# napajeniMOB.net
KiCad netlist of a schematic drawn in EAGLE
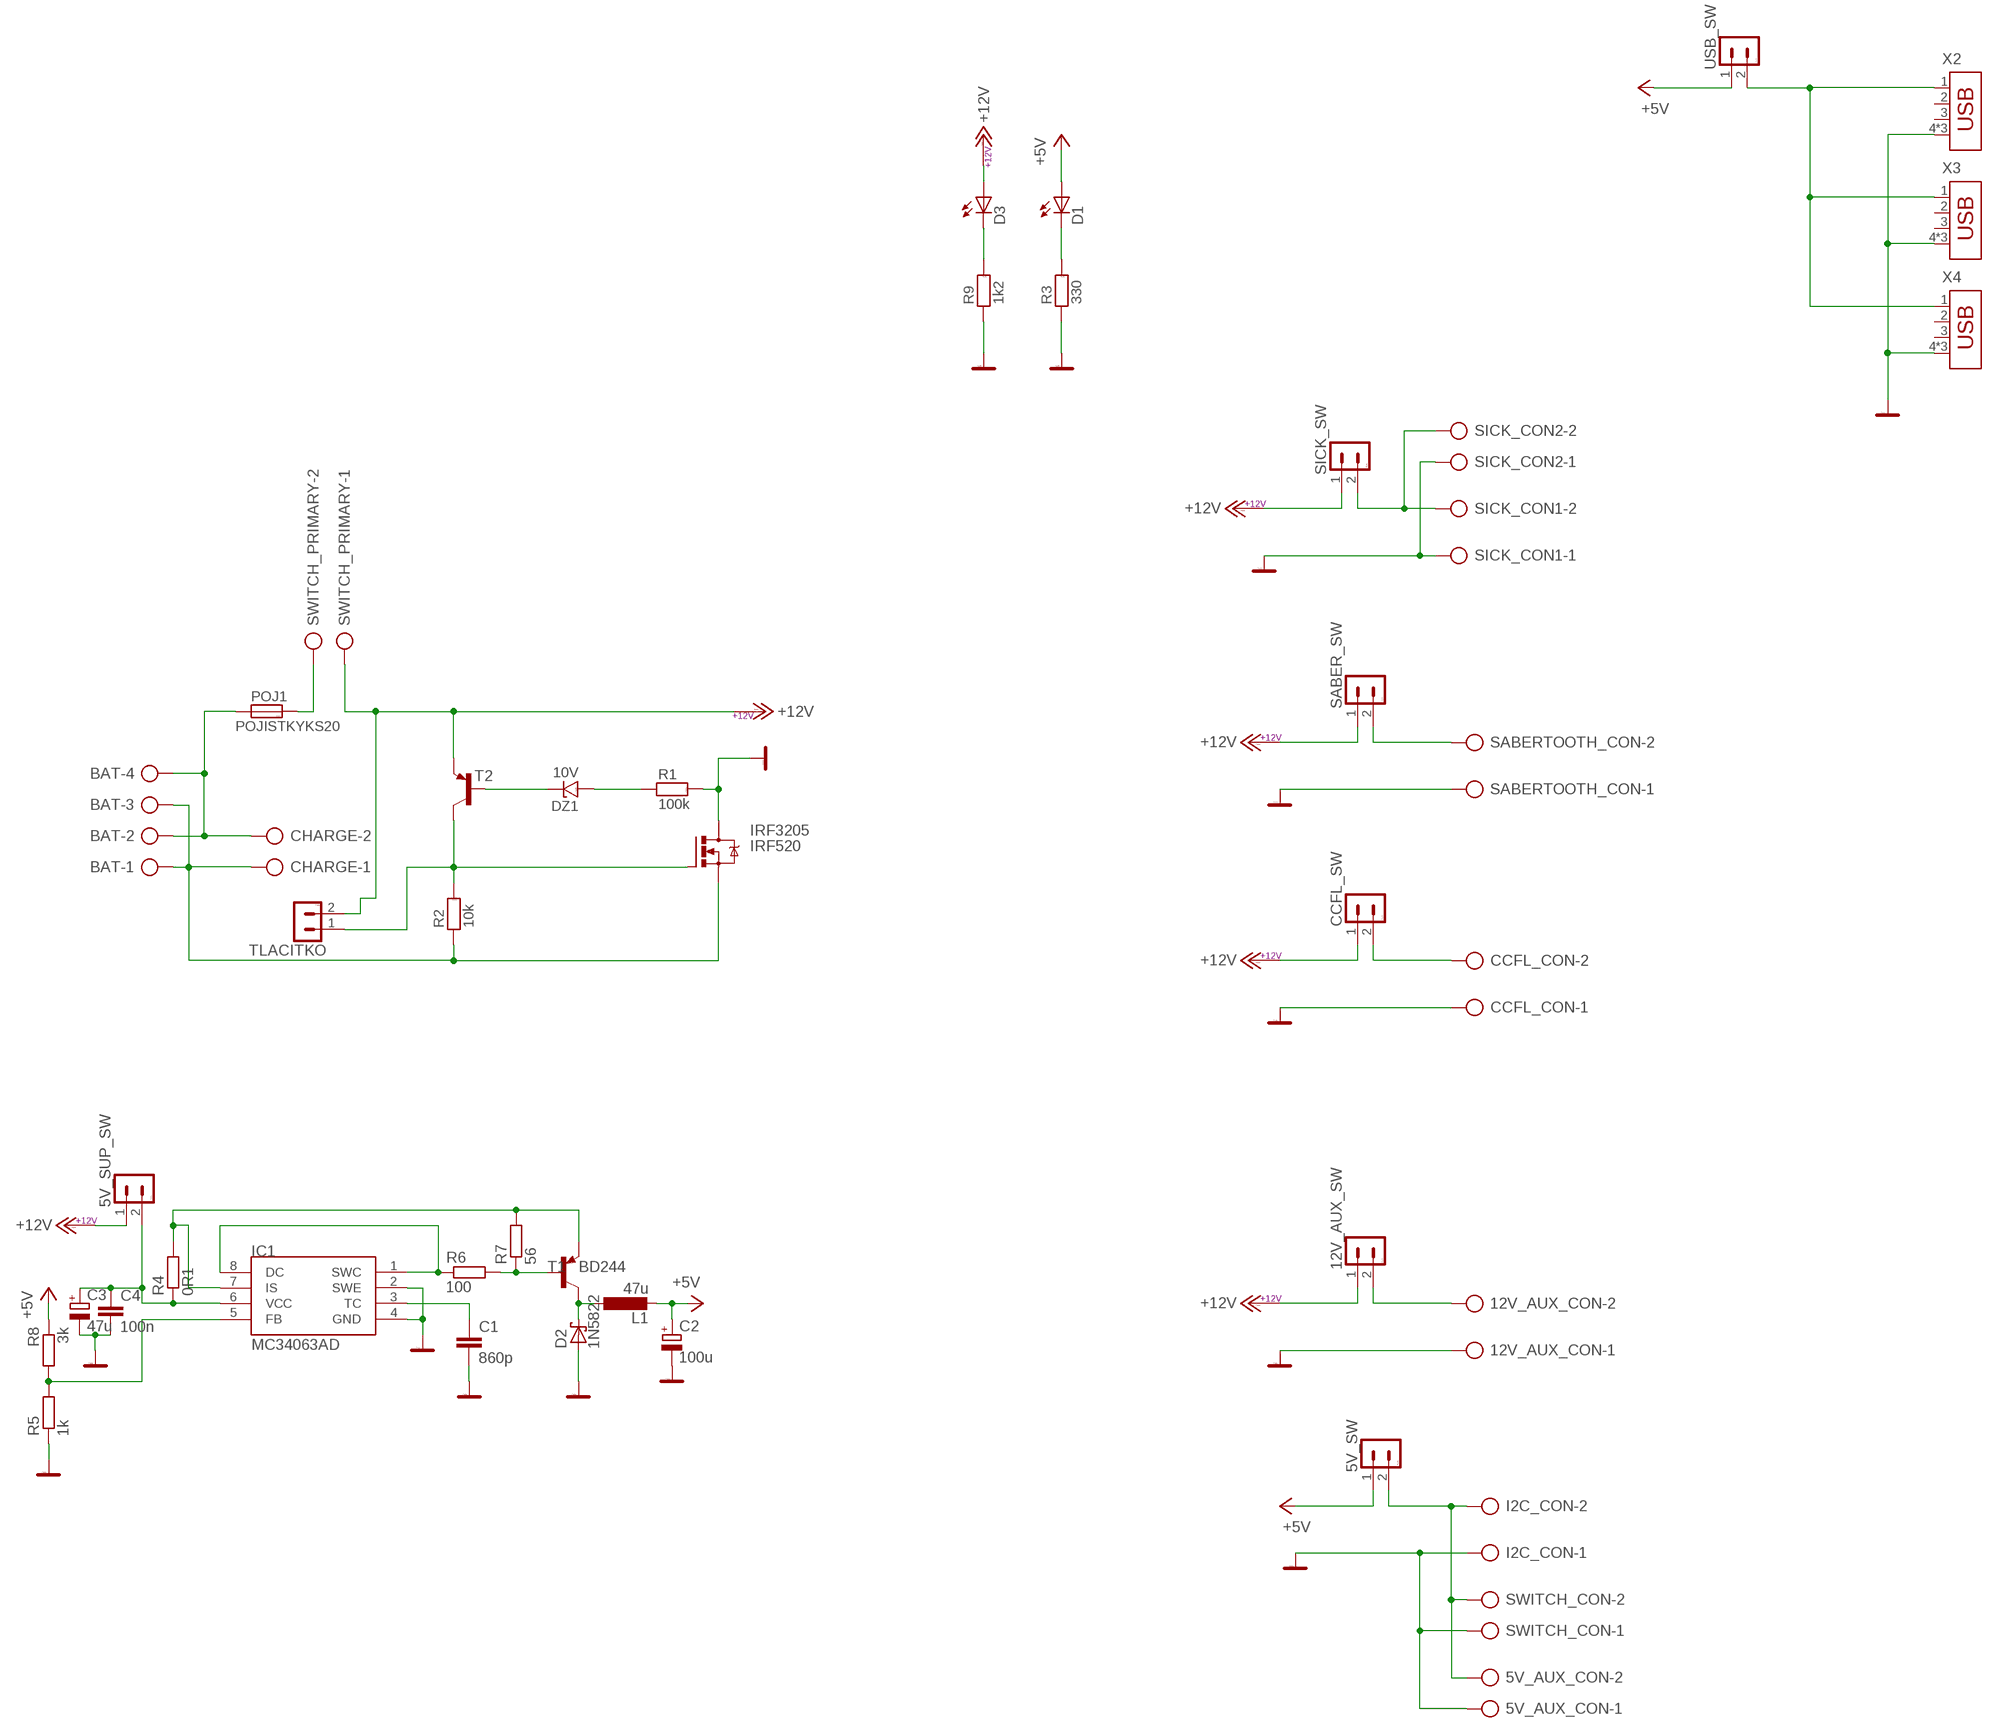
[diagram p0: schematic, sheet 1]

(export (version "E")
  (design (tool "Eeschema 10.0.6"))
  (components
    (comp (ref "5V_AUX_CON")
      (value "AK500/2")
      (footprint "eagle-import:AK500_2")
      (libsource (lib "eagle-import") (part "AK500/2"))
    )
    (comp (ref "5V_SUP_SW")
      (value "PSH02-02P")
      (footprint "eagle-import:PSH02-02P")
      (libsource (lib "eagle-import") (part "PSH02-02P"))
    )
    (comp (ref "5V_SW")
      (value "PSH02-02P")
      (footprint "eagle-import:PSH02-02P")
      (libsource (lib "eagle-import") (part "PSH02-02P"))
    )
    (comp (ref "12V_AUX_CON")
      (value "AK500/2")
      (footprint "eagle-import:AK500_2")
      (libsource (lib "eagle-import") (part "AK500/2"))
    )
    (comp (ref "12V_AUX_SW")
      (value "PSH02-02P")
      (footprint "eagle-import:PSH02-02P")
      (libsource (lib "eagle-import") (part "PSH02-02P"))
    )
    (comp (ref "BAT")
      (value "AK500/4")
      (footprint "eagle-import:AK500_4")
      (libsource (lib "eagle-import") (part "AK500/4"))
    )
    (comp (ref "C1")
      (value "860p")
      (footprint "eagle-import:C0805")
      (libsource (lib "eagle-import") (part "C-EUC0805"))
    )
    (comp (ref "C2")
      (value "100u")
      (footprint "eagle-import:E5-8,5")
      (libsource (lib "eagle-import") (part "CPOL-EUE5-8.5"))
    )
    (comp (ref "C3")
      (value "47u")
      (footprint "eagle-import:E5-8,5")
      (libsource (lib "eagle-import") (part "CPOL-EUE5-8.5"))
    )
    (comp (ref "C4")
      (value "100n")
      (footprint "eagle-import:C0805")
      (libsource (lib "eagle-import") (part "C-EUC0805"))
    )
    (comp (ref "CCFL_CON")
      (value "AK500/2")
      (footprint "eagle-import:AK500_2")
      (libsource (lib "eagle-import") (part "AK500/2"))
    )
    (comp (ref "CCFL_SW")
      (value "PSH02-02P")
      (footprint "eagle-import:PSH02-02P")
      (libsource (lib "eagle-import") (part "PSH02-02P"))
    )
    (comp (ref "CHARGE")
      (value "AK500/2")
      (footprint "eagle-import:AK500_2")
      (libsource (lib "eagle-import") (part "AK500/2"))
    )
    (comp (ref "D1")
      (value "LED3MM")
      (footprint "eagle-import:LED3MM")
      (libsource (lib "eagle-import") (part "LED3MM"))
    )
    (comp (ref "D2")
      (value "1N5822")
      (footprint "eagle-import:DO41-7.6")
      (libsource (lib "eagle-import") (part "1N5817-B"))
    )
    (comp (ref "D3")
      (value "LED3MM")
      (footprint "eagle-import:LED3MM")
      (libsource (lib "eagle-import") (part "LED3MM"))
    )
    (comp (ref "DZ1")
      (value "10V")
      (footprint "eagle-import:SOD-80")
      (libsource (lib "eagle-import") (part "D-ZENEROVA_0,5W_BZV55C_SMD"))
    )
    (comp (ref "I2C_CON")
      (value "AK500/2")
      (footprint "eagle-import:AK500_2")
      (libsource (lib "eagle-import") (part "AK500/2"))
    )
    (comp (ref "IC1")
      (value "MC34063AD")
      (footprint "eagle-import:SOIC8")
      (libsource (lib "eagle-import") (part "MC34063AD"))
    )
    (comp (ref "IRF3205")
      (value "IRF520")
      (footprint "eagle-import:TO220BV")
      (libsource (lib "eagle-import") (part "IRF520"))
    )
    (comp (ref "L1")
      (value "47u")
      (footprint "eagle-import:TJ3-U1")
      (libsource (lib "eagle-import") (part "L-EUTJ3-U1"))
    )
    (comp (ref "POJ1")
      (value "POJISTKYKS20")
      (footprint "eagle-import:POJ_KS20")
      (libsource (lib "eagle-import") (part "POJISTKYKS20"))
    )
    (comp (ref "R1")
      (value "100k")
      (footprint "eagle-import:0805")
      (libsource (lib "eagle-import") (part "R_SMD_0805"))
    )
    (comp (ref "R2")
      (value "10k")
      (footprint "eagle-import:0805")
      (libsource (lib "eagle-import") (part "R_SMD_0805"))
    )
    (comp (ref "R3")
      (value "330")
      (footprint "eagle-import:0805")
      (libsource (lib "eagle-import") (part "R_SMD_0805"))
    )
    (comp (ref "R4")
      (value "0R1")
      (footprint "eagle-import:M0805")
      (libsource (lib "eagle-import") (part "R-EU_M0805"))
    )
    (comp (ref "R5")
      (value "1k")
      (footprint "eagle-import:M0805")
      (libsource (lib "eagle-import") (part "R-EU_M0805"))
    )
    (comp (ref "R6")
      (value "100")
      (footprint "eagle-import:M0805")
      (libsource (lib "eagle-import") (part "R-EU_M0805"))
    )
    (comp (ref "R7")
      (value "56")
      (footprint "eagle-import:M0805")
      (libsource (lib "eagle-import") (part "R-EU_M0805"))
    )
    (comp (ref "R8")
      (value "3k")
      (footprint "eagle-import:M0805")
      (libsource (lib "eagle-import") (part "R-EU_M0805"))
    )
    (comp (ref "R9")
      (value "1k2")
      (footprint "eagle-import:0805")
      (libsource (lib "eagle-import") (part "R_SMD_0805"))
    )
    (comp (ref "SABERTOOTH_CON")
      (value "AK500/2")
      (footprint "eagle-import:AK500_2")
      (libsource (lib "eagle-import") (part "AK500/2"))
    )
    (comp (ref "SABER_SW")
      (value "PSH02-02P")
      (footprint "eagle-import:PSH02-02P")
      (libsource (lib "eagle-import") (part "PSH02-02P"))
    )
    (comp (ref "SICK_CON1")
      (value "AK500/2")
      (footprint "eagle-import:AK500_2")
      (libsource (lib "eagle-import") (part "AK500/2"))
    )
    (comp (ref "SICK_CON2")
      (value "AK500/2")
      (footprint "eagle-import:AK500_2")
      (libsource (lib "eagle-import") (part "AK500/2"))
    )
    (comp (ref "SICK_SW")
      (value "PSH02-02P")
      (footprint "eagle-import:PSH02-02P")
      (libsource (lib "eagle-import") (part "PSH02-02P"))
    )
    (comp (ref "SWITCH_CON")
      (value "AK500/2")
      (footprint "eagle-import:AK500_2")
      (libsource (lib "eagle-import") (part "AK500/2"))
    )
    (comp (ref "SWITCH_PRIMARY")
      (value "AK500/2")
      (footprint "eagle-import:AK500_2")
      (libsource (lib "eagle-import") (part "AK500/2"))
    )
    (comp (ref "T1")
      (value "BD244")
      (footprint "eagle-import:TO220")
      (libsource (lib "eagle-import") (part "BD244"))
    )
    (comp (ref "T2")
      (value "BC807-16-PNP-SOT23-BEC")
      (footprint "eagle-import:SOT23-BEC")
      (libsource (lib "eagle-import") (part "-PNP-SOT23-BECBC807-16"))
    )
    (comp (ref "TLACITKO")
      (value "PSH02-02P")
      (footprint "eagle-import:PSH02-02P")
      (libsource (lib "eagle-import") (part "PSH02-02P"))
    )
    (comp (ref "USB_SW")
      (value "PSH02-02P")
      (footprint "eagle-import:PSH02-02P")
      (libsource (lib "eagle-import") (part "PSH02-02P"))
    )
    (comp (ref "X2")
      (value "USB-787616GROUNDED")
      (footprint "eagle-import:USBGROUNDED")
      (libsource (lib "eagle-import") (part "USB-787616GROUNDED"))
    )
    (comp (ref "X3")
      (value "USB-787616GROUNDED")
      (footprint "eagle-import:USBGROUNDED")
      (libsource (lib "eagle-import") (part "USB-787616GROUNDED"))
    )
    (comp (ref "X4")
      (value "USB-787616GROUNDED")
      (footprint "eagle-import:USBGROUNDED")
      (libsource (lib "eagle-import") (part "USB-787616GROUNDED"))
    )
  )
  (nets
    (net (code "1") (name "+5V") (class "Default")
      (node (ref "5V_SW") (pin "1") (pinfunction "1_1") (pintype "passive"))
      (node (ref "C2") (pin "+") (pinfunction "+_+") (pintype "passive"))
      (node (ref "D1") (pin "A") (pinfunction "A_A") (pintype "passive"))
      (node (ref "L1") (pin "2") (pinfunction "2_2") (pintype "passive"))
      (node (ref "R8") (pin "1") (pinfunction "1_1") (pintype "passive"))
      (node (ref "USB_SW") (pin "1") (pinfunction "1_1") (pintype "passive"))
    )
    (net (code "2") (name "+12V") (class "Default")
      (node (ref "12V_AUX_SW") (pin "1") (pinfunction "1_1") (pintype "passive"))
      (node (ref "5V_SUP_SW") (pin "1") (pinfunction "1_1") (pintype "passive"))
      (node (ref "CCFL_SW") (pin "1") (pinfunction "1_1") (pintype "passive"))
      (node (ref "D3") (pin "A") (pinfunction "A_A") (pintype "passive"))
      (node (ref "SABER_SW") (pin "1") (pinfunction "1_1") (pintype "passive"))
      (node (ref "SICK_SW") (pin "1") (pinfunction "1_1") (pintype "passive"))
      (node (ref "SWITCH_PRIMARY") (pin "1") (pinfunction "KL_1") (pintype "passive"))
      (node (ref "T2") (pin "E") (pinfunction "E_E") (pintype "passive"))
      (node (ref "TLACITKO") (pin "2") (pinfunction "2_2") (pintype "passive"))
    )
    (net (code "3") (name "GND") (class "Default")
      (node (ref "12V_AUX_CON") (pin "1") (pinfunction "KL_1") (pintype "passive"))
      (node (ref "5V_AUX_CON") (pin "1") (pinfunction "KL_1") (pintype "passive"))
      (node (ref "C1") (pin "2") (pinfunction "2_2") (pintype "passive"))
      (node (ref "C2") (pin "-") (pinfunction "-_-") (pintype "passive"))
      (node (ref "C3") (pin "-") (pinfunction "-_-") (pintype "passive"))
      (node (ref "C4") (pin "2") (pinfunction "2_2") (pintype "passive"))
      (node (ref "CCFL_CON") (pin "1") (pinfunction "KL_1") (pintype "passive"))
      (node (ref "D2") (pin "A") (pinfunction "A_A") (pintype "passive"))
      (node (ref "I2C_CON") (pin "1") (pinfunction "KL_1") (pintype "passive"))
      (node (ref "IC1") (pin "2") (pinfunction "SWE_2") (pintype "passive"))
      (node (ref "IC1") (pin "4") (pinfunction "GND_4") (pintype "passive"))
      (node (ref "IRF3205") (pin "D") (pinfunction "D_D") (pintype "passive"))
      (node (ref "R1") (pin "2") (pinfunction "2_2") (pintype "passive"))
      (node (ref "R3") (pin "1") (pinfunction "1_1") (pintype "passive"))
      (node (ref "R5") (pin "1") (pinfunction "1_1") (pintype "passive"))
      (node (ref "R9") (pin "1") (pinfunction "1_1") (pintype "passive"))
      (node (ref "SABERTOOTH_CON") (pin "1") (pinfunction "KL_1") (pintype "passive"))
      (node (ref "SICK_CON1") (pin "1") (pinfunction "KL_1") (pintype "passive"))
      (node (ref "SICK_CON2") (pin "1") (pinfunction "KL_1") (pintype "passive"))
      (node (ref "SWITCH_CON") (pin "1") (pinfunction "KL_1") (pintype "passive"))
      (node (ref "X2") (pin "4") (pinfunction "4_4") (pintype "passive"))
      (node (ref "X2") (pin "S1") (pinfunction "4_S1") (pintype "passive"))
      (node (ref "X2") (pin "S2") (pinfunction "4_S2") (pintype "passive"))
      (node (ref "X3") (pin "4") (pinfunction "4_4") (pintype "passive"))
      (node (ref "X3") (pin "S1") (pinfunction "4_S1") (pintype "passive"))
      (node (ref "X3") (pin "S2") (pinfunction "4_S2") (pintype "passive"))
      (node (ref "X4") (pin "4") (pinfunction "4_4") (pintype "passive"))
      (node (ref "X4") (pin "S1") (pinfunction "4_S1") (pintype "passive"))
      (node (ref "X4") (pin "S2") (pinfunction "4_S2") (pintype "passive"))
    )
    (net (code "4") (name "Net-(5V_AUX_CONB-KL)") (class "Default")
      (node (ref "5V_AUX_CON") (pin "2") (pinfunction "KL_2") (pintype "passive"))
      (node (ref "5V_SW") (pin "2") (pinfunction "2_2") (pintype "passive"))
      (node (ref "I2C_CON") (pin "2") (pinfunction "KL_2") (pintype "passive"))
      (node (ref "SWITCH_CON") (pin "2") (pinfunction "KL_2") (pintype "passive"))
    )
    (net (code "5") (name "Net-(12V_AUX_CONB-KL)") (class "Default")
      (node (ref "12V_AUX_CON") (pin "2") (pinfunction "KL_2") (pintype "passive"))
      (node (ref "12V_AUX_SW") (pin "2") (pinfunction "2_2") (pintype "passive"))
    )
    (net (code "6") (name "Net-(BATA-KL)") (class "Default")
      (node (ref "BAT") (pin "1") (pinfunction "KL_1") (pintype "passive"))
      (node (ref "BAT") (pin "3") (pinfunction "KL_3") (pintype "passive"))
      (node (ref "CHARGE") (pin "1") (pinfunction "KL_1") (pintype "passive"))
      (node (ref "IRF3205") (pin "S") (pinfunction "S_S") (pintype "passive"))
      (node (ref "R2") (pin "1") (pinfunction "1_1") (pintype "passive"))
    )
    (net (code "7") (name "Net-(BATB-KL)") (class "Default")
      (node (ref "BAT") (pin "2") (pinfunction "KL_2") (pintype "passive"))
      (node (ref "BAT") (pin "4") (pinfunction "KL_4") (pintype "passive"))
      (node (ref "CHARGE") (pin "2") (pinfunction "KL_2") (pintype "passive"))
      (node (ref "POJ1") (pin "1") (pinfunction "1_1") (pintype "passive"))
    )
    (net (code "8") (name "Net-(CCFL_CONB-KL)") (class "Default")
      (node (ref "CCFL_CON") (pin "2") (pinfunction "KL_2") (pintype "passive"))
      (node (ref "CCFL_SW") (pin "2") (pinfunction "2_2") (pintype "passive"))
    )
    (net (code "9") (name "Net-(D1-C)") (class "Default")
      (node (ref "D1") (pin "K") (pinfunction "C_K") (pintype "passive"))
      (node (ref "R3") (pin "2") (pinfunction "2_2") (pintype "passive"))
    )
    (net (code "10") (name "Net-(D3-C)") (class "Default")
      (node (ref "D3") (pin "K") (pinfunction "C_K") (pintype "passive"))
      (node (ref "R9") (pin "2") (pinfunction "2_2") (pintype "passive"))
    )
    (net (code "11") (name "Net-(DZ1-PadA)") (class "Default")
      (node (ref "DZ1") (pin "A") (pinfunction "A_A") (pintype "passive"))
      (node (ref "R1") (pin "1") (pinfunction "1_1") (pintype "passive"))
    )
    (net (code "12") (name "Net-(DZ1-PadK)") (class "Default")
      (node (ref "DZ1") (pin "K") (pinfunction "K_K") (pintype "passive"))
      (node (ref "T2") (pin "B") (pinfunction "B_B") (pintype "passive"))
    )
    (net (code "13") (name "Net-(IC1-DC)") (class "Default")
      (node (ref "IC1") (pin "1") (pinfunction "SWC_1") (pintype "passive"))
      (node (ref "IC1") (pin "8") (pinfunction "DC_8") (pintype "passive"))
      (node (ref "R6") (pin "1") (pinfunction "1_1") (pintype "passive"))
    )
    (net (code "14") (name "Net-(IC1-FB)") (class "Default")
      (node (ref "IC1") (pin "5") (pinfunction "FB_5") (pintype "passive"))
      (node (ref "R5") (pin "2") (pinfunction "2_2") (pintype "passive"))
      (node (ref "R8") (pin "2") (pinfunction "2_2") (pintype "passive"))
    )
    (net (code "15") (name "Net-(IC1-IS)") (class "Default")
      (node (ref "IC1") (pin "7") (pinfunction "IS_7") (pintype "passive"))
      (node (ref "R4") (pin "2") (pinfunction "2_2") (pintype "passive"))
      (node (ref "R7") (pin "2") (pinfunction "2_2") (pintype "passive"))
      (node (ref "T1") (pin "3") (pinfunction "E_3") (pintype "passive"))
    )
    (net (code "16") (name "Net-(IC1-TC)") (class "Default")
      (node (ref "C1") (pin "1") (pinfunction "1_1") (pintype "passive"))
      (node (ref "IC1") (pin "3") (pinfunction "TC_3") (pintype "passive"))
    )
    (net (code "17") (name "Net-(IC1-VCC)") (class "Default")
      (node (ref "5V_SUP_SW") (pin "2") (pinfunction "2_2") (pintype "passive"))
      (node (ref "C3") (pin "+") (pinfunction "+_+") (pintype "passive"))
      (node (ref "C4") (pin "1") (pinfunction "1_1") (pintype "passive"))
      (node (ref "IC1") (pin "6") (pinfunction "VCC_6") (pintype "passive"))
      (node (ref "R4") (pin "1") (pinfunction "1_1") (pintype "passive"))
    )
    (net (code "18") (name "Net-(IRF3205-PadG)") (class "Default")
      (node (ref "IRF3205") (pin "G") (pinfunction "G_G") (pintype "passive"))
      (node (ref "R2") (pin "2") (pinfunction "2_2") (pintype "passive"))
      (node (ref "T2") (pin "C") (pinfunction "C_C") (pintype "passive"))
      (node (ref "TLACITKO") (pin "1") (pinfunction "1_1") (pintype "passive"))
    )
    (net (code "19") (name "Net-(SABERTOOTH_CONB-KL)") (class "Default")
      (node (ref "SABERTOOTH_CON") (pin "2") (pinfunction "KL_2") (pintype "passive"))
      (node (ref "SABER_SW") (pin "2") (pinfunction "2_2") (pintype "passive"))
    )
    (net (code "20") (name "Net-(SICK_CON1B-KL)") (class "Default")
      (node (ref "SICK_CON1") (pin "2") (pinfunction "KL_2") (pintype "passive"))
      (node (ref "SICK_CON2") (pin "2") (pinfunction "KL_2") (pintype "passive"))
      (node (ref "SICK_SW") (pin "2") (pinfunction "2_2") (pintype "passive"))
    )
    (net (code "21") (name "Net-(SWITCH_PRIMARYB-KL)") (class "Default")
      (node (ref "POJ1") (pin "2") (pinfunction "2_2") (pintype "passive"))
      (node (ref "SWITCH_PRIMARY") (pin "2") (pinfunction "KL_2") (pintype "passive"))
    )
    (net (code "22") (name "Net-(T1-B)") (class "Default")
      (node (ref "R6") (pin "2") (pinfunction "2_2") (pintype "passive"))
      (node (ref "R7") (pin "1") (pinfunction "1_1") (pintype "passive"))
      (node (ref "T1") (pin "1") (pinfunction "B_1") (pintype "passive"))
    )
    (net (code "23") (name "Net-(T1-C)") (class "Default")
      (node (ref "D2") (pin "C") (pinfunction "C_C") (pintype "passive"))
      (node (ref "L1") (pin "1") (pinfunction "1_1") (pintype "passive"))
      (node (ref "T1") (pin "2") (pinfunction "C_2") (pintype "passive"))
    )
    (net (code "24") (name "Net-(USB_SW-Pad2)") (class "Default")
      (node (ref "USB_SW") (pin "2") (pinfunction "2_2") (pintype "passive"))
      (node (ref "X2") (pin "1") (pinfunction "1_1") (pintype "passive"))
      (node (ref "X3") (pin "1") (pinfunction "1_1") (pintype "passive"))
      (node (ref "X4") (pin "1") (pinfunction "1_1") (pintype "passive"))
    )
    (net (code "25") (name "unconnected-(X2-Pad2)") (class "Default")
      (node (ref "X2") (pin "2") (pinfunction "2_2") (pintype "passive"))
    )
    (net (code "26") (name "unconnected-(X2-Pad3)") (class "Default")
      (node (ref "X2") (pin "3") (pinfunction "3_3") (pintype "passive"))
    )
    (net (code "27") (name "unconnected-(X3-Pad2)") (class "Default")
      (node (ref "X3") (pin "2") (pinfunction "2_2") (pintype "passive"))
    )
    (net (code "28") (name "unconnected-(X3-Pad3)") (class "Default")
      (node (ref "X3") (pin "3") (pinfunction "3_3") (pintype "passive"))
    )
    (net (code "29") (name "unconnected-(X4-Pad2)") (class "Default")
      (node (ref "X4") (pin "2") (pinfunction "2_2") (pintype "passive"))
    )
    (net (code "30") (name "unconnected-(X4-Pad3)") (class "Default")
      (node (ref "X4") (pin "3") (pinfunction "3_3") (pintype "passive"))
    )
  )
)
